# Base_Station_1_7.net
KiCad netlist of a schematic drawn in EAGLE
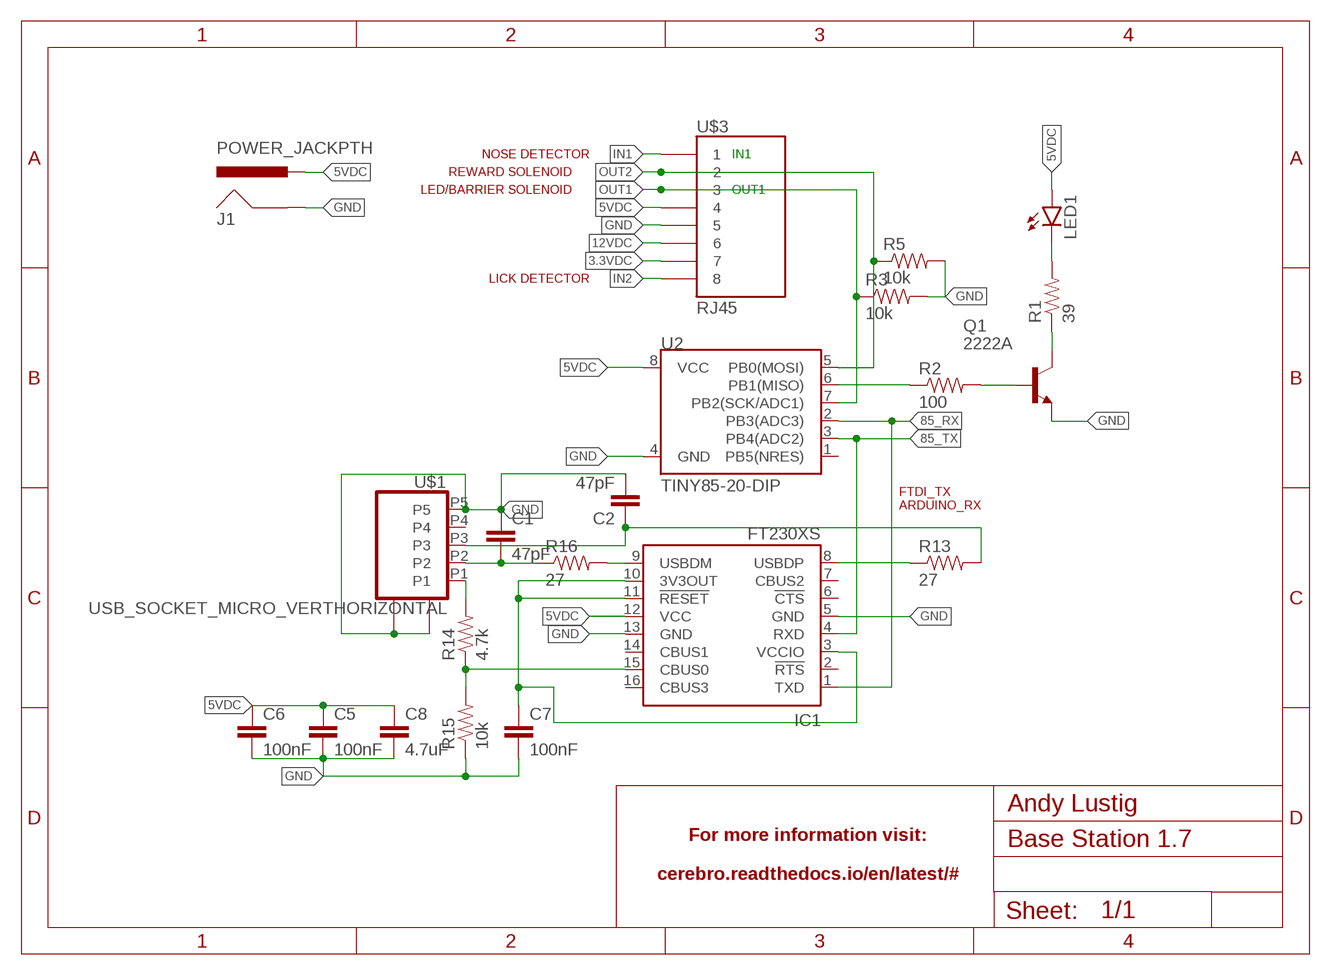
[diagram p0: schematic, sheet 1]

(export (version "E")
  (design (tool "Eeschema 10.0.6"))
  (components
    (comp (ref "C1")
      (value "47pF")
      (footprint "eagle-import:CAP-PTH-SMALL")
      (libsource (lib "eagle-import") (part "CAPPTH"))
    )
    (comp (ref "C2")
      (value "47pF")
      (footprint "eagle-import:CAP-PTH-SMALL")
      (libsource (lib "eagle-import") (part "CAPPTH"))
    )
    (comp (ref "C5")
      (value "100nF")
      (footprint "eagle-import:CAP-PTH-SMALL")
      (libsource (lib "eagle-import") (part "CAPPTH"))
    )
    (comp (ref "C6")
      (value "100nF")
      (footprint "eagle-import:CAP-PTH-SMALL")
      (libsource (lib "eagle-import") (part "CAPPTH"))
    )
    (comp (ref "C7")
      (value "100nF")
      (footprint "eagle-import:CAP-PTH-SMALL")
      (libsource (lib "eagle-import") (part "CAPPTH"))
    )
    (comp (ref "C8")
      (value "4.7uF")
      (footprint "eagle-import:CAP-PTH-SMALL")
      (libsource (lib "eagle-import") (part "CAPPTH"))
    )
    (comp (ref "IC1")
      (value "FT230XS")
      (footprint "eagle-import:SSOP16")
      (libsource (lib "eagle-import") (part "FT230XS"))
    )
    (comp (ref "J1")
      (value "POWER_JACKPTH")
      (footprint "eagle-import:POWER_JACK_PTH")
      (libsource (lib "eagle-import") (part "POWER_JACKPTH"))
    )
    (comp (ref "LED1")
      (value "LED")
      (footprint "eagle-import:PLCC-2")
      (libsource (lib "eagle-import") (part "LED"))
    )
    (comp (ref "Q1")
      (value "2222A")
      (footprint "eagle-import:TO92-EBC-OVAL")
      (libsource (lib "eagle-import") (part "2N2222"))
    )
    (comp (ref "R1")
      (value "39")
      (footprint "eagle-import:AXIAL-0.1")
      (libsource (lib "eagle-import") (part "RESISTORPTH-1/4W-VERT"))
    )
    (comp (ref "R2")
      (value "100")
      (footprint "eagle-import:AXIAL-0.1")
      (libsource (lib "eagle-import") (part "RESISTORPTH-1/4W-VERT"))
    )
    (comp (ref "R3")
      (value "10k")
      (footprint "eagle-import:AXIAL-0.1")
      (libsource (lib "eagle-import") (part "RESISTORPTH-1/4W-VERT"))
    )
    (comp (ref "R5")
      (value "10k")
      (footprint "eagle-import:AXIAL-0.1")
      (libsource (lib "eagle-import") (part "RESISTORPTH-1/4W-VERT"))
    )
    (comp (ref "R13")
      (value "27")
      (footprint "eagle-import:AXIAL-0.1")
      (libsource (lib "eagle-import") (part "RESISTORPTH-1/4W-VERT"))
    )
    (comp (ref "R14")
      (value "4.7k")
      (footprint "eagle-import:AXIAL-0.1")
      (libsource (lib "eagle-import") (part "RESISTORPTH-1/4W-VERT"))
    )
    (comp (ref "R15")
      (value "10k")
      (footprint "eagle-import:AXIAL-0.1")
      (libsource (lib "eagle-import") (part "RESISTORPTH-1/4W-VERT"))
    )
    (comp (ref "R16")
      (value "27")
      (footprint "eagle-import:AXIAL-0.1")
      (libsource (lib "eagle-import") (part "RESISTORPTH-1/4W-VERT"))
    )
    (comp (ref "U$1")
      (value "USB_SOCKET_MICRO_VERTHORIZONTAL")
      (footprint "eagle-import:USB_HORZ_MICRO_SMD")
      (libsource (lib "eagle-import") (part "USB_SOCKET_MICRO_VERTHORIZONTAL"))
    )
    (comp (ref "U$3")
      (value "RJ45")
      (footprint "eagle-import:RJ45-8")
      (libsource (lib "eagle-import") (part "RJ45"))
    )
    (comp (ref "U2")
      (value "TINY85-20-DIP")
      (footprint "eagle-import:DIP08")
      (libsource (lib "eagle-import") (part "ATTINY45TINY85-20-DIP"))
    )
  )
  (nets
    (net (code "1") (name "3.3VDC") (class "Default")
      (node (ref "U$3") (pin "7") (pinfunction "7_7") (pintype "bidirectional"))
    )
    (net (code "2") (name "5VDC") (class "Default")
      (node (ref "C5") (pin "1") (pinfunction "1_1") (pintype "passive"))
      (node (ref "C6") (pin "1") (pinfunction "1_1") (pintype "passive"))
      (node (ref "C8") (pin "1") (pinfunction "1_1") (pintype "passive"))
      (node (ref "IC1") (pin "12") (pinfunction "VCC_12") (pintype "power_in"))
      (node (ref "J1") (pin "PWR") (pinfunction "PWR_PWR") (pintype "bidirectional"))
      (node (ref "LED1") (pin "ANODE") (pinfunction "A_ANODE") (pintype "passive"))
      (node (ref "U$3") (pin "4") (pinfunction "4_4") (pintype "bidirectional"))
      (node (ref "U2") (pin "8") (pinfunction "VCC_8") (pintype "bidirectional"))
    )
    (net (code "3") (name "12VDC") (class "Default")
      (node (ref "U$3") (pin "6") (pinfunction "6_6") (pintype "bidirectional"))
    )
    (net (code "4") (name "85_RX") (class "Default")
      (node (ref "IC1") (pin "1") (pinfunction "TXD_1") (pintype "output"))
      (node (ref "U2") (pin "2") (pinfunction "PB3(ADC3)_2") (pintype "bidirectional"))
    )
    (net (code "5") (name "85_TX") (class "Default")
      (node (ref "IC1") (pin "4") (pinfunction "RXD_4") (pintype "input"))
      (node (ref "U2") (pin "3") (pinfunction "PB4(ADC2)_3") (pintype "bidirectional"))
    )
    (net (code "6") (name "GND") (class "Default")
      (node (ref "C1") (pin "1") (pinfunction "1_1") (pintype "passive"))
      (node (ref "C2") (pin "2") (pinfunction "2_2") (pintype "passive"))
      (node (ref "C5") (pin "2") (pinfunction "2_2") (pintype "passive"))
      (node (ref "C6") (pin "2") (pinfunction "2_2") (pintype "passive"))
      (node (ref "C7") (pin "2") (pinfunction "2_2") (pintype "passive"))
      (node (ref "C8") (pin "2") (pinfunction "2_2") (pintype "passive"))
      (node (ref "IC1") (pin "13") (pinfunction "GND_13") (pintype "power_in"))
      (node (ref "IC1") (pin "5") (pinfunction "GND_5") (pintype "power_in"))
      (node (ref "J1") (pin "GND") (pinfunction "GND_GND") (pintype "bidirectional"))
      (node (ref "Q1") (pin "E") (pinfunction "E_E") (pintype "passive"))
      (node (ref "R15") (pin "P$1") (pinfunction "1_P$1") (pintype "passive"))
      (node (ref "R3") (pin "P$2") (pinfunction "2_P$2") (pintype "passive"))
      (node (ref "R5") (pin "P$2") (pinfunction "2_P$2") (pintype "passive"))
      (node (ref "U$1") (pin "G1") (pinfunction "P$1_G1") (pintype "bidirectional"))
      (node (ref "U$1") (pin "G2") (pinfunction "P$2_G2") (pintype "bidirectional"))
      (node (ref "U$1") (pin "P5") (pinfunction "P5_P5") (pintype "bidirectional"))
      (node (ref "U$3") (pin "5") (pinfunction "5_5") (pintype "bidirectional"))
      (node (ref "U2") (pin "4") (pinfunction "GND_4") (pintype "bidirectional"))
    )
    (net (code "7") (name "IN1") (class "Default")
      (node (ref "U$3") (pin "1") (pinfunction "1_1") (pintype "bidirectional"))
    )
    (net (code "8") (name "IN2") (class "Default")
      (node (ref "U$3") (pin "8") (pinfunction "8_8") (pintype "bidirectional"))
    )
    (net (code "9") (name "Net-(IC1-3V3OUT)") (class "Default")
      (node (ref "C7") (pin "1") (pinfunction "1_1") (pintype "passive"))
      (node (ref "IC1") (pin "10") (pinfunction "3V3OUT_10") (pintype "output"))
      (node (ref "IC1") (pin "11") (pinfunction "~{RESET}_11") (pintype "input"))
      (node (ref "IC1") (pin "3") (pinfunction "VCCIO_3") (pintype "power_in"))
    )
    (net (code "10") (name "Net-(IC1-CBUS0)") (class "Default")
      (node (ref "IC1") (pin "15") (pinfunction "CBUS0_15") (pintype "bidirectional"))
      (node (ref "R14") (pin "P$1") (pinfunction "1_P$1") (pintype "passive"))
      (node (ref "R15") (pin "P$2") (pinfunction "2_P$2") (pintype "passive"))
    )
    (net (code "11") (name "Net-(IC1-USBDM)") (class "Default")
      (node (ref "IC1") (pin "9") (pinfunction "USBDM_9") (pintype "input"))
      (node (ref "R16") (pin "P$2") (pinfunction "2_P$2") (pintype "passive"))
    )
    (net (code "12") (name "Net-(IC1-USBDP)") (class "Default")
      (node (ref "IC1") (pin "8") (pinfunction "USBDP_8") (pintype "input"))
      (node (ref "R13") (pin "P$1") (pinfunction "1_P$1") (pintype "passive"))
    )
    (net (code "13") (name "Net-(LED1-C)") (class "Default")
      (node (ref "LED1") (pin "CATHODE") (pinfunction "C_CATHODE") (pintype "passive"))
      (node (ref "R1") (pin "P$2") (pinfunction "2_P$2") (pintype "passive"))
    )
    (net (code "14") (name "Net-(R1-1)") (class "Default")
      (node (ref "Q1") (pin "C") (pinfunction "C_C") (pintype "passive"))
      (node (ref "R1") (pin "P$1") (pinfunction "1_P$1") (pintype "passive"))
    )
    (net (code "15") (name "Net-(R2-1)") (class "Default")
      (node (ref "R2") (pin "P$1") (pinfunction "1_P$1") (pintype "passive"))
      (node (ref "U2") (pin "6") (pinfunction "PB1(MISO)_6") (pintype "bidirectional"))
    )
    (net (code "16") (name "Net-(R2-2)") (class "Default")
      (node (ref "Q1") (pin "B") (pinfunction "B_B") (pintype "passive"))
      (node (ref "R2") (pin "P$2") (pinfunction "2_P$2") (pintype "passive"))
    )
    (net (code "17") (name "Net-(R13-2)") (class "Default")
      (node (ref "C2") (pin "1") (pinfunction "1_1") (pintype "passive"))
      (node (ref "R13") (pin "P$2") (pinfunction "2_P$2") (pintype "passive"))
      (node (ref "U$1") (pin "P3") (pinfunction "P3_P3") (pintype "bidirectional"))
    )
    (net (code "18") (name "Net-(R14-2)") (class "Default")
      (node (ref "R14") (pin "P$2") (pinfunction "2_P$2") (pintype "passive"))
      (node (ref "U$1") (pin "P1") (pinfunction "P1_P1") (pintype "bidirectional"))
    )
    (net (code "19") (name "Net-(R16-1)") (class "Default")
      (node (ref "C1") (pin "2") (pinfunction "2_2") (pintype "passive"))
      (node (ref "R16") (pin "P$1") (pinfunction "1_P$1") (pintype "passive"))
      (node (ref "U$1") (pin "P2") (pinfunction "P2_P2") (pintype "bidirectional"))
    )
    (net (code "20") (name "OUT1") (class "Default")
      (node (ref "R3") (pin "P$1") (pinfunction "1_P$1") (pintype "passive"))
      (node (ref "U$3") (pin "3") (pinfunction "3_3") (pintype "bidirectional"))
      (node (ref "U2") (pin "7") (pinfunction "PB2(SCK/ADC1)_7") (pintype "bidirectional"))
    )
    (net (code "21") (name "OUT2") (class "Default")
      (node (ref "R5") (pin "P$1") (pinfunction "1_P$1") (pintype "passive"))
      (node (ref "U$3") (pin "2") (pinfunction "2_2") (pintype "bidirectional"))
      (node (ref "U2") (pin "5") (pinfunction "PB0(MOSI)_5") (pintype "bidirectional"))
    )
    (net (code "22") (name "unconnected-(IC1-CBUS1-Pad14)") (class "Default")
      (node (ref "IC1") (pin "14") (pinfunction "CBUS1_14") (pintype "bidirectional"))
    )
    (net (code "23") (name "unconnected-(IC1-CBUS2-Pad7)") (class "Default")
      (node (ref "IC1") (pin "7") (pinfunction "CBUS2_7") (pintype "bidirectional"))
    )
    (net (code "24") (name "unconnected-(IC1-CBUS3-Pad16)") (class "Default")
      (node (ref "IC1") (pin "16") (pinfunction "CBUS3_16") (pintype "bidirectional"))
    )
    (net (code "25") (name "unconnected-(IC1-~{CTS}-Pad6)") (class "Default")
      (node (ref "IC1") (pin "6") (pinfunction "~{CTS}_6") (pintype "input"))
    )
    (net (code "26") (name "unconnected-(IC1-~{RTS}-Pad2)") (class "Default")
      (node (ref "IC1") (pin "2") (pinfunction "~{RTS}_2") (pintype "output"))
    )
    (net (code "27") (name "unconnected-(U$1-PadP4)") (class "Default")
      (node (ref "U$1") (pin "P4") (pinfunction "P4_P4") (pintype "bidirectional"))
    )
    (net (code "28") (name "unconnected-(U2-PB5(NRES)-Pad1)") (class "Default")
      (node (ref "U2") (pin "1") (pinfunction "PB5(NRES)_1") (pintype "bidirectional"))
    )
  )
)
